# GPS.net
KiCad netlist of a schematic drawn in Altium Designer
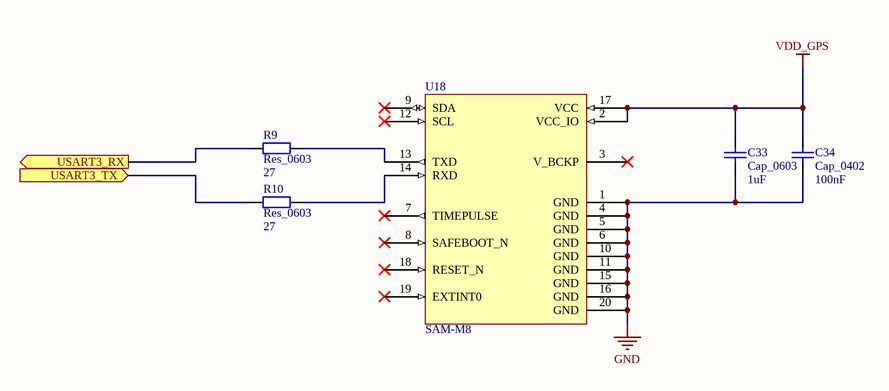
[diagram p0: GPS.SchDoc]

(export (version "E")
  (design (tool "Eeschema 10.0.6"))
  (components
    (comp (ref "C33")
      (value "Cap_0603")
      (footprint "0603")
      (description "Capacitor")
      (fields (field (name "ALTIUM_VALUE") "1uF") (field (name "PUBLISHER") "Altium Limited"))
      (libsource (lib "Schematic_Components") (part "Cap_0603"))
    )
    (comp (ref "C34")
      (value "Cap_0402")
      (footprint "0402")
      (description "Capacitor")
      (fields (field (name "ALTIUM_VALUE") "100nF") (field (name "PUBLISHER") "Altium Limited"))
      (libsource (lib "Schematic_Components") (part "Cap_0402"))
    )
    (comp (ref "R9")
      (value "Res_0603")
      (footprint "0603")
      (description "Resistor")
      (fields (field (name "ALTIUM_VALUE") "27") (field (name "PUBLISHER") "Altium Limited"))
      (libsource (lib "Schematic_Components") (part "Res_0603"))
    )
    (comp (ref "R10")
      (value "Res_0603")
      (footprint "0603")
      (description "Resistor")
      (fields (field (name "ALTIUM_VALUE") "27") (field (name "PUBLISHER") "Altium Limited"))
      (libsource (lib "Schematic_Components") (part "Res_0603"))
    )
    (comp (ref "U18")
      (value "SAM-M8")
      (footprint "SAM-M8")
      (description "GNSS moduleS")
      (libsource (lib "Schematic_Components") (part "SAM-M8"))
    )
  )
  (nets
    (net (code "1") (name "/USART3_RX") (class "Default")
      (node (ref "R9") (pin "1") (pinfunction "1_1") (pintype "passive"))
    )
    (net (code "2") (name "/USART3_TX") (class "Default")
      (node (ref "R10") (pin "1") (pinfunction "1_1") (pintype "passive"))
    )
    (net (code "3") (name "GND") (class "Default")
      (node (ref "C33") (pin "1") (pinfunction "1_1") (pintype "passive"))
      (node (ref "C34") (pin "1") (pinfunction "1_1") (pintype "passive"))
      (node (ref "U18") (pin "1") (pinfunction "GND_1") (pintype "passive"))
      (node (ref "U18") (pin "10") (pinfunction "GND_10") (pintype "passive"))
      (node (ref "U18") (pin "11") (pinfunction "GND_11") (pintype "passive"))
      (node (ref "U18") (pin "15") (pinfunction "GND_15") (pintype "passive"))
      (node (ref "U18") (pin "16") (pinfunction "GND_16") (pintype "passive"))
      (node (ref "U18") (pin "20") (pinfunction "GND_20") (pintype "passive"))
      (node (ref "U18") (pin "4") (pinfunction "GND_4") (pintype "passive"))
      (node (ref "U18") (pin "5") (pinfunction "GND_5") (pintype "passive"))
      (node (ref "U18") (pin "6") (pinfunction "GND_6") (pintype "passive"))
    )
    (net (code "4") (name "Net-(U18-RXD)") (class "Default")
      (node (ref "R10") (pin "2") (pinfunction "2_2") (pintype "passive"))
      (node (ref "U18") (pin "14") (pinfunction "RXD_14") (pintype "input"))
    )
    (net (code "5") (name "Net-(U18-TXD)") (class "Default")
      (node (ref "R9") (pin "2") (pinfunction "2_2") (pintype "passive"))
      (node (ref "U18") (pin "13") (pinfunction "TXD_13") (pintype "output"))
    )
    (net (code "6") (name "VDD_GPS") (class "Default")
      (node (ref "C33") (pin "2") (pinfunction "2_2") (pintype "passive"))
      (node (ref "C34") (pin "2") (pinfunction "2_2") (pintype "passive"))
      (node (ref "U18") (pin "17") (pinfunction "VCC_17") (pintype "input"))
      (node (ref "U18") (pin "2") (pinfunction "VCC_IO_2") (pintype "input"))
    )
    (net (code "7") (name "unconnected-(U18-EXTINT0-Pad19)") (class "Default")
      (node (ref "U18") (pin "19") (pinfunction "EXTINT0_19") (pintype "input+no_connect"))
    )
    (net (code "8") (name "unconnected-(U18-RESET_N-Pad18)") (class "Default")
      (node (ref "U18") (pin "18") (pinfunction "RESET_N_18") (pintype "input+no_connect"))
    )
    (net (code "9") (name "unconnected-(U18-SAFEBOOT_N-Pad8)") (class "Default")
      (node (ref "U18") (pin "8") (pinfunction "SAFEBOOT_N_8") (pintype "input+no_connect"))
    )
    (net (code "10") (name "unconnected-(U18-SCL-Pad12)") (class "Default")
      (node (ref "U18") (pin "12") (pinfunction "SCL_12") (pintype "input+no_connect"))
    )
    (net (code "11") (name "unconnected-(U18-SDA-Pad9)") (class "Default")
      (node (ref "U18") (pin "9") (pinfunction "SDA_9") (pintype "bidirectional+no_connect"))
    )
    (net (code "12") (name "unconnected-(U18-TIMEPULSE-Pad7)") (class "Default")
      (node (ref "U18") (pin "7") (pinfunction "TIMEPULSE_7") (pintype "output+no_connect"))
    )
    (net (code "13") (name "unconnected-(U18-V_BCKP-Pad3)") (class "Default")
      (node (ref "U18") (pin "3") (pinfunction "V_BCKP_3") (pintype "power_in+no_connect"))
    )
  )
)
